# LED_RGBLight_AD_1.net
KiCad netlist of a schematic drawn in Altium Designer
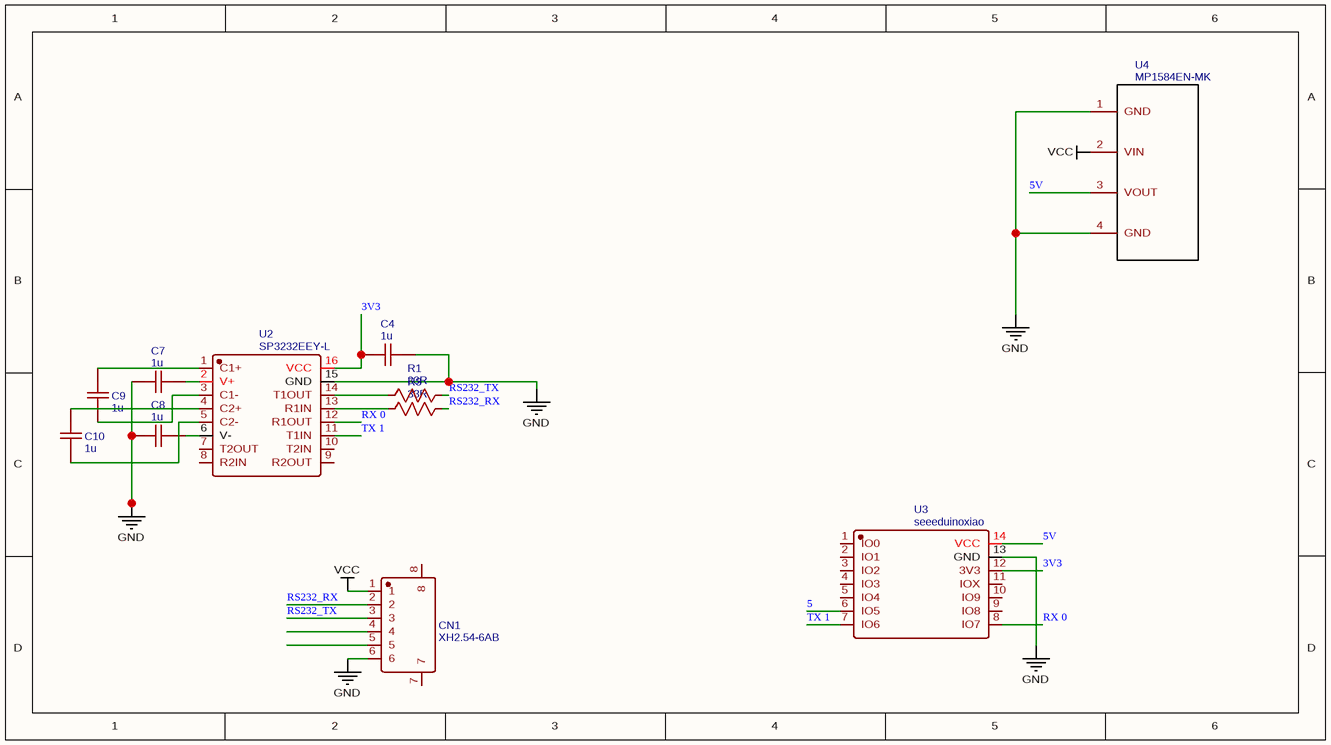
[diagram p0: LED_RGBLight_AD (1).schdoc]

(export (version "E")
  (design (tool "Eeschema 10.0.6"))
  (components
    (comp (ref "C4")
      (value "1u")
      (fields (field (name "CONTRIBUTOR") "LCEDA_Lib"))
      (libsource (lib "altium-import") (part "root_0_1u_"))
    )
    (comp (ref "C7")
      (value "1u")
      (fields (field (name "CONTRIBUTOR") "LCEDA_Lib"))
      (libsource (lib "altium-import") (part "root_2_1u_"))
    )
    (comp (ref "C8")
      (value "1u")
      (fields (field (name "CONTRIBUTOR") "LCEDA_Lib"))
      (libsource (lib "altium-import") (part "root_2_1u_"))
    )
    (comp (ref "C9")
      (value "1u")
      (fields (field (name "CONTRIBUTOR") "LCEDA_Lib"))
      (libsource (lib "altium-import") (part "root_1_1u_"))
    )
    (comp (ref "C10")
      (value "1u")
      (fields (field (name "CONTRIBUTOR") "LCEDA_Lib"))
      (libsource (lib "altium-import") (part "root_1_1u_"))
    )
    (comp (ref "CN1")
      (value "XH2.54-6AB")
      (fields (field (name "BOM_SUPPLIER PART") "C146129") (field (name "CONTRIBUTOR") "LCSC"))
      (libsource (lib "altium-import") (part "root_0_XH2.54-6AB_"))
    )
    (comp (ref "R1")
      (value "33R")
      (fields (field (name "CONTRIBUTOR") "LCEDA_Lib"))
      (libsource (lib "altium-import") (part "root_0_33R_"))
    )
    (comp (ref "R3")
      (value "33R")
      (fields (field (name "CONTRIBUTOR") "LCEDA_Lib"))
      (libsource (lib "altium-import") (part "root_0_33R_"))
    )
    (comp (ref "U2")
      (value "SP3232EEY-L")
      (fields (field (name "BOM_SUPPLIER PART") "C2692307") (field (name "CONTRIBUTOR") "LCSC"))
      (libsource (lib "altium-import") (part "root_0_SP3232EEY-L_"))
    )
    (comp (ref "U3")
      (value "seeeduinoxiao")
      (fields (field (name "CONTRIBUTOR") "StephenTXZ"))
      (libsource (lib "altium-import") (part "root_0_seeeduinoxiao_"))
    )
    (comp (ref "U4")
      (value "MP1584EN-MK")
      (fields (field (name "CONTRIBUTOR") "Ssu7828"))
      (libsource (lib "altium-import") (part "root_0_MP1584EN-MK_"))
    )
  )
  (nets
    (net (code "1") (name "/3V3") (class "Default")
      (node (ref "C4") (pin "1") (pinfunction "1_1") (pintype "passive"))
      (node (ref "U2") (pin "16") (pinfunction "VCC_16") (pintype "passive"))
      (node (ref "U3") (pin "12") (pinfunction "3V3_12") (pintype "passive"))
    )
    (net (code "2") (name "/5") (class "Default")
      (node (ref "U3") (pin "6") (pinfunction "IO5_6") (pintype "passive"))
    )
    (net (code "3") (name "/5V") (class "Default")
      (node (ref "U3") (pin "14") (pinfunction "VCC_14") (pintype "passive"))
      (node (ref "U4") (pin "3") (pinfunction "VOUT_3") (pintype "passive"))
    )
    (net (code "4") (name "/RS232_RX") (class "Default")
      (node (ref "CN1") (pin "2") (pinfunction "2_2") (pintype "passive"))
      (node (ref "R3") (pin "2") (pinfunction "2_2") (pintype "passive"))
    )
    (net (code "5") (name "/RS232_TX") (class "Default")
      (node (ref "CN1") (pin "3") (pinfunction "3_3") (pintype "passive"))
      (node (ref "R1") (pin "2") (pinfunction "2_2") (pintype "passive"))
    )
    (net (code "6") (name "/RX 0") (class "Default")
      (node (ref "U2") (pin "12") (pinfunction "R1OUT_12") (pintype "passive"))
      (node (ref "U3") (pin "8") (pinfunction "IO7_8") (pintype "passive"))
    )
    (net (code "7") (name "/TX 1") (class "Default")
      (node (ref "U2") (pin "11") (pinfunction "T1IN_11") (pintype "passive"))
      (node (ref "U3") (pin "7") (pinfunction "IO6_7") (pintype "passive"))
    )
    (net (code "8") (name "GND") (class "Default")
      (node (ref "C4") (pin "2") (pinfunction "2_2") (pintype "passive"))
      (node (ref "C7") (pin "2") (pinfunction "2_2") (pintype "passive"))
      (node (ref "C8") (pin "2") (pinfunction "2_2") (pintype "passive"))
      (node (ref "CN1") (pin "6") (pinfunction "6_6") (pintype "passive"))
      (node (ref "U2") (pin "15") (pinfunction "GND_15") (pintype "passive"))
      (node (ref "U3") (pin "13") (pinfunction "GND_13") (pintype "passive"))
      (node (ref "U4") (pin "1") (pinfunction "GND_1") (pintype "passive"))
      (node (ref "U4") (pin "4") (pinfunction "GND_4") (pintype "passive"))
    )
    (net (code "9") (name "Net-(U2-C1+)") (class "Default")
      (node (ref "C9") (pin "2") (pinfunction "2_2") (pintype "passive"))
      (node (ref "U2") (pin "1") (pinfunction "C1+_1") (pintype "passive"))
    )
    (net (code "10") (name "Net-(U2-C1-)") (class "Default")
      (node (ref "C9") (pin "1") (pinfunction "1_1") (pintype "passive"))
      (node (ref "U2") (pin "3") (pinfunction "C1-_3") (pintype "passive"))
    )
    (net (code "11") (name "Net-(U2-C2+)") (class "Default")
      (node (ref "C10") (pin "2") (pinfunction "2_2") (pintype "passive"))
      (node (ref "U2") (pin "4") (pinfunction "C2+_4") (pintype "passive"))
    )
    (net (code "12") (name "Net-(U2-C2-)") (class "Default")
      (node (ref "C10") (pin "1") (pinfunction "1_1") (pintype "passive"))
      (node (ref "U2") (pin "5") (pinfunction "C2-_5") (pintype "passive"))
    )
    (net (code "13") (name "Net-(U2-R1IN)") (class "Default")
      (node (ref "R3") (pin "1") (pinfunction "1_1") (pintype "passive"))
      (node (ref "U2") (pin "13") (pinfunction "R1IN_13") (pintype "passive"))
    )
    (net (code "14") (name "Net-(U2-T1OUT)") (class "Default")
      (node (ref "R1") (pin "1") (pinfunction "1_1") (pintype "passive"))
      (node (ref "U2") (pin "14") (pinfunction "T1OUT_14") (pintype "passive"))
    )
    (net (code "15") (name "Net-(U2-V+)") (class "Default")
      (node (ref "C7") (pin "1") (pinfunction "1_1") (pintype "passive"))
      (node (ref "U2") (pin "2") (pinfunction "V+_2") (pintype "passive"))
    )
    (net (code "16") (name "Net-(U2-V-)") (class "Default")
      (node (ref "C8") (pin "1") (pinfunction "1_1") (pintype "passive"))
      (node (ref "U2") (pin "6") (pinfunction "V-_6") (pintype "passive"))
    )
    (net (code "17") (name "VCC") (class "Default")
      (node (ref "CN1") (pin "1") (pinfunction "1_1") (pintype "passive"))
      (node (ref "U4") (pin "2") (pinfunction "VIN_2") (pintype "passive"))
    )
    (net (code "18") (name "unconnected-(CN1-Pad4)") (class "Default")
      (node (ref "CN1") (pin "4") (pinfunction "4_4") (pintype "passive"))
    )
    (net (code "19") (name "unconnected-(CN1-Pad5)") (class "Default")
      (node (ref "CN1") (pin "5") (pinfunction "5_5") (pintype "passive"))
    )
    (net (code "20") (name "unconnected-(CN1-Pad7)") (class "Default")
      (node (ref "CN1") (pin "7") (pinfunction "7_7") (pintype "passive"))
    )
    (net (code "21") (name "unconnected-(CN1-Pad8)") (class "Default")
      (node (ref "CN1") (pin "8") (pinfunction "8_8") (pintype "passive"))
    )
    (net (code "22") (name "unconnected-(U2-R2IN-Pad8)") (class "Default")
      (node (ref "U2") (pin "8") (pinfunction "R2IN_8") (pintype "passive"))
    )
    (net (code "23") (name "unconnected-(U2-R2OUT-Pad9)") (class "Default")
      (node (ref "U2") (pin "9") (pinfunction "R2OUT_9") (pintype "passive"))
    )
    (net (code "24") (name "unconnected-(U2-T2IN-Pad10)") (class "Default")
      (node (ref "U2") (pin "10") (pinfunction "T2IN_10") (pintype "passive"))
    )
    (net (code "25") (name "unconnected-(U2-T2OUT-Pad7)") (class "Default")
      (node (ref "U2") (pin "7") (pinfunction "T2OUT_7") (pintype "passive"))
    )
    (net (code "26") (name "unconnected-(U3-IO0-Pad1)") (class "Default")
      (node (ref "U3") (pin "1") (pinfunction "IO0_1") (pintype "passive"))
    )
    (net (code "27") (name "unconnected-(U3-IO1-Pad2)") (class "Default")
      (node (ref "U3") (pin "2") (pinfunction "IO1_2") (pintype "passive"))
    )
    (net (code "28") (name "unconnected-(U3-IO2-Pad3)") (class "Default")
      (node (ref "U3") (pin "3") (pinfunction "IO2_3") (pintype "passive"))
    )
    (net (code "29") (name "unconnected-(U3-IO3-Pad4)") (class "Default")
      (node (ref "U3") (pin "4") (pinfunction "IO3_4") (pintype "passive"))
    )
    (net (code "30") (name "unconnected-(U3-IO4-Pad5)") (class "Default")
      (node (ref "U3") (pin "5") (pinfunction "IO4_5") (pintype "passive"))
    )
    (net (code "31") (name "unconnected-(U3-IO8-Pad9)") (class "Default")
      (node (ref "U3") (pin "9") (pinfunction "IO8_9") (pintype "passive"))
    )
    (net (code "32") (name "unconnected-(U3-IO9-Pad10)") (class "Default")
      (node (ref "U3") (pin "10") (pinfunction "IO9_10") (pintype "passive"))
    )
    (net (code "33") (name "unconnected-(U3-IOX-Pad11)") (class "Default")
      (node (ref "U3") (pin "11") (pinfunction "IOX_11") (pintype "passive"))
    )
  )
)
